# lpf.net
KiCad netlist of a schematic drawn in Altium Designer
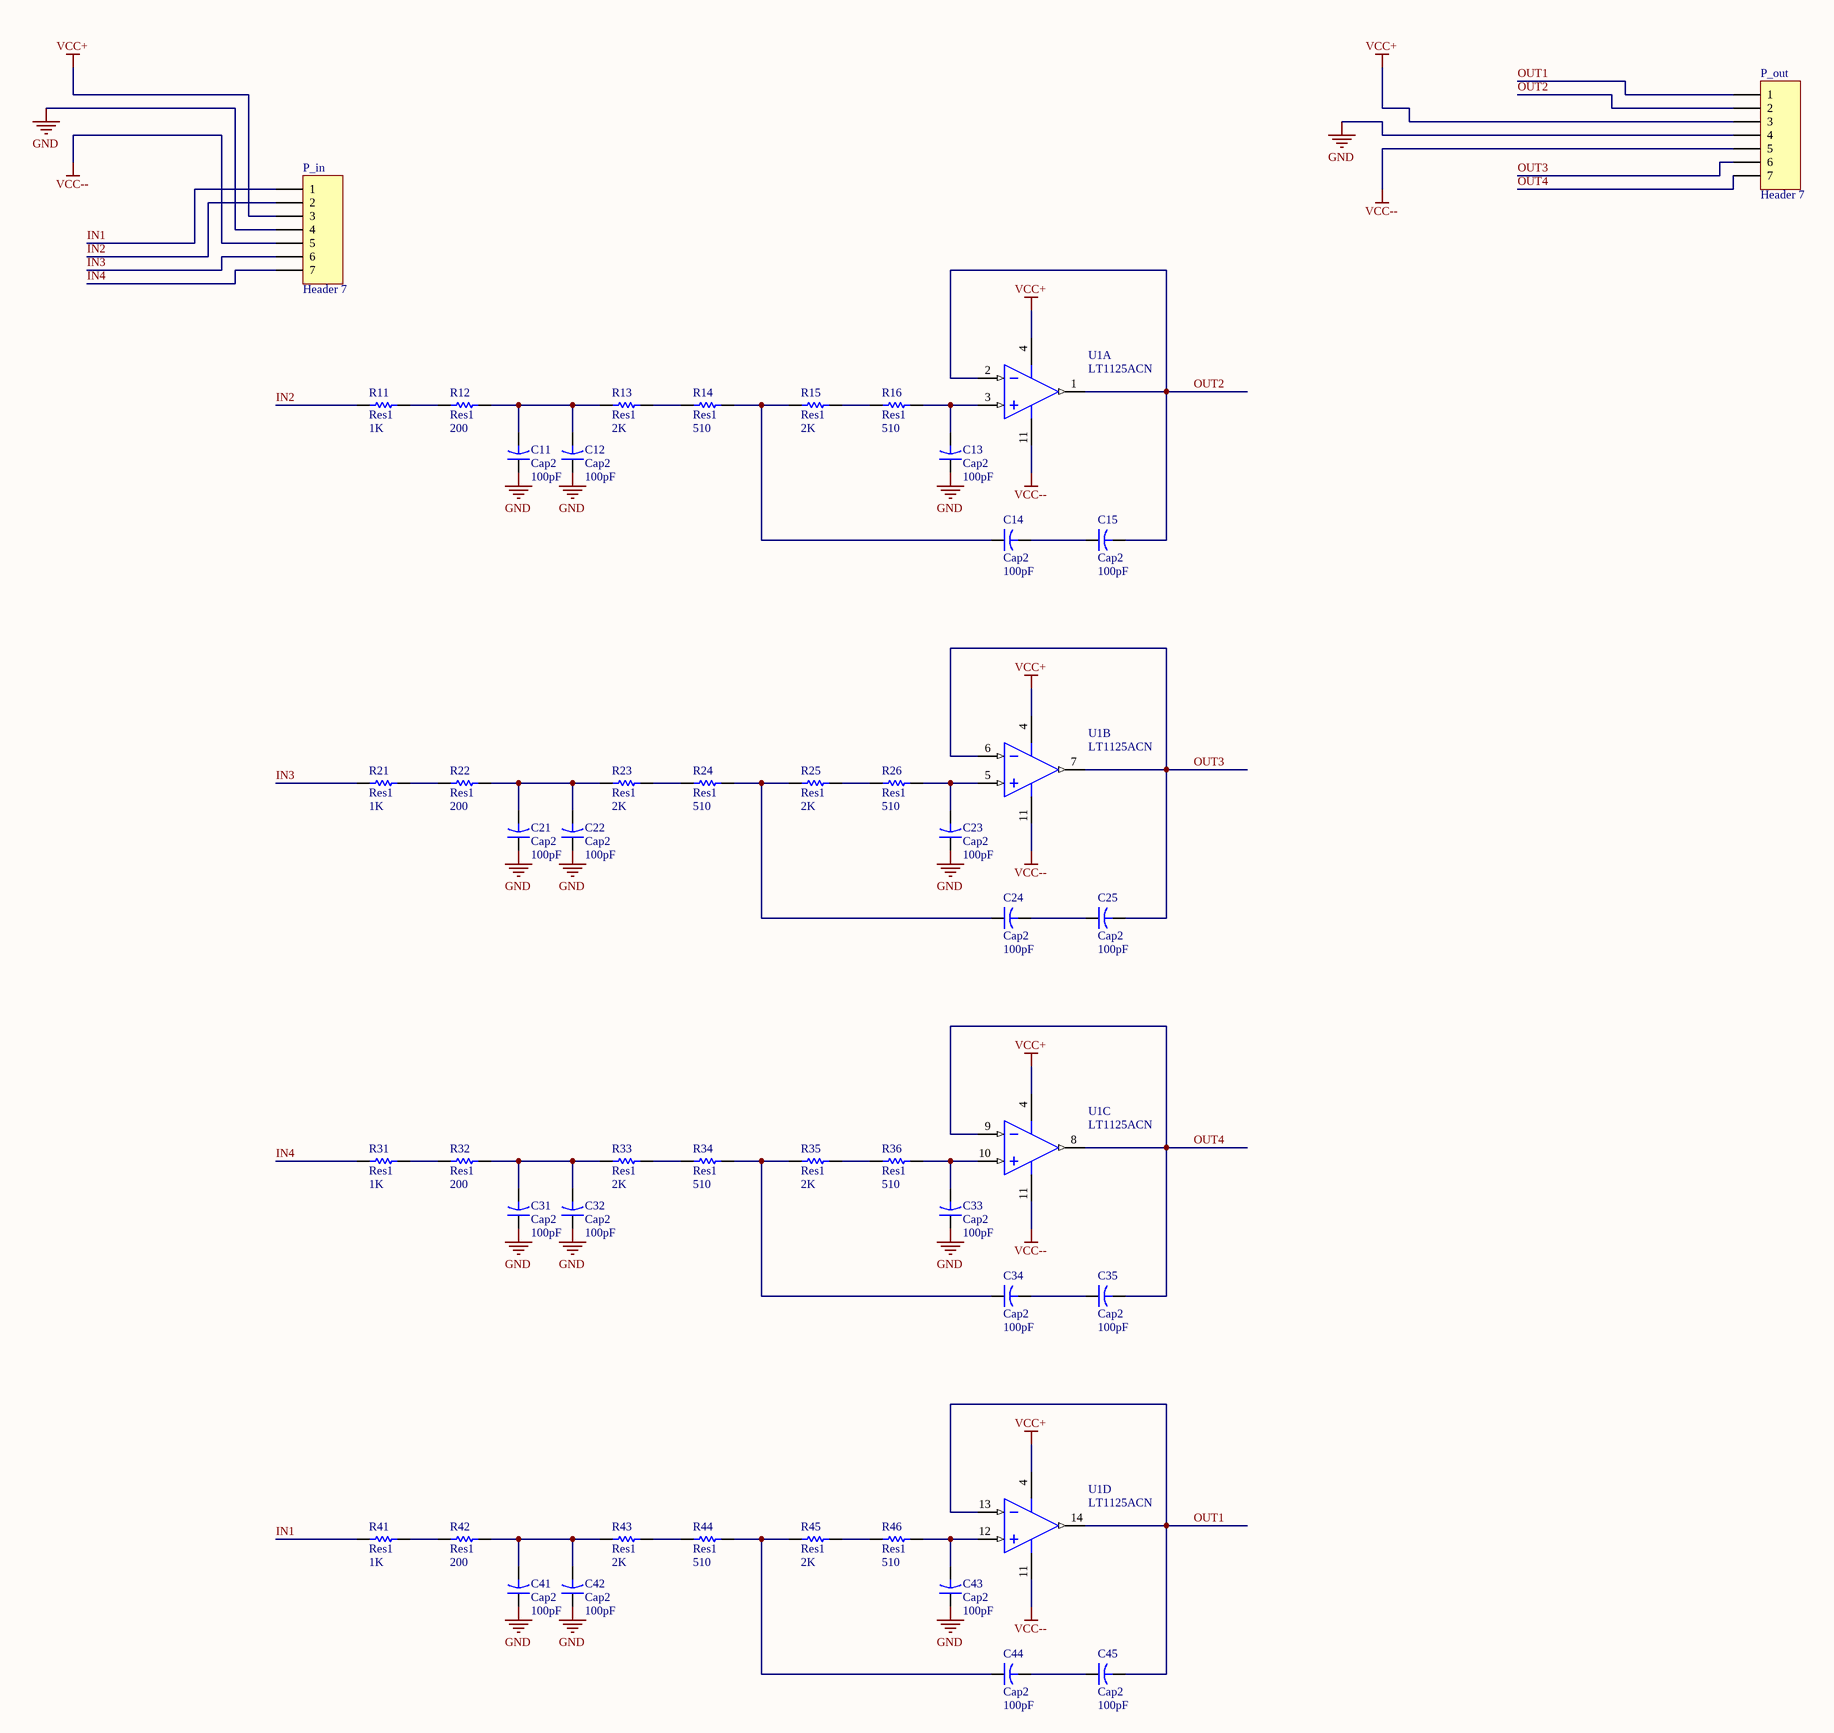
[diagram p0: lpf.SchDoc]

(export (version "E")
  (design (tool "Eeschema 10.0.6"))
  (components
    (comp (ref "C11")
      (value "Cap2")
      (footprint "CAPR5-4X5")
      (description "Capacitor")
      (fields (field (name "ALTIUM_VALUE") "100pF") (field (name "PUBLISHER") "Altium Limited"))
      (libsource (lib "Miscellaneous Devices") (part "Cap2"))
    )
    (comp (ref "C12")
      (value "Cap2")
      (footprint "CAPR5-4X5")
      (description "Capacitor")
      (fields (field (name "ALTIUM_VALUE") "100pF") (field (name "PUBLISHER") "Altium Limited"))
      (libsource (lib "Miscellaneous Devices") (part "Cap2"))
    )
    (comp (ref "C13")
      (value "Cap2")
      (footprint "CAPR5-4X5")
      (description "Capacitor")
      (fields (field (name "ALTIUM_VALUE") "100pF") (field (name "PUBLISHER") "Altium Limited"))
      (libsource (lib "Miscellaneous Devices") (part "Cap2"))
    )
    (comp (ref "C14")
      (value "Cap2")
      (footprint "CAPR5-4X5")
      (description "Capacitor")
      (fields (field (name "ALTIUM_VALUE") "100pF") (field (name "PUBLISHER") "Altium Limited"))
      (libsource (lib "Miscellaneous Devices") (part "Cap2"))
    )
    (comp (ref "C15")
      (value "Cap2")
      (footprint "CAPR5-4X5")
      (description "Capacitor")
      (fields (field (name "ALTIUM_VALUE") "100pF") (field (name "PUBLISHER") "Altium Limited"))
      (libsource (lib "Miscellaneous Devices") (part "Cap2"))
    )
    (comp (ref "C21")
      (value "Cap2")
      (footprint "CAPR5-4X5")
      (description "Capacitor")
      (fields (field (name "ALTIUM_VALUE") "100pF") (field (name "PUBLISHER") "Altium Limited"))
      (libsource (lib "Miscellaneous Devices") (part "Cap2"))
    )
    (comp (ref "C22")
      (value "Cap2")
      (footprint "CAPR5-4X5")
      (description "Capacitor")
      (fields (field (name "ALTIUM_VALUE") "100pF") (field (name "PUBLISHER") "Altium Limited"))
      (libsource (lib "Miscellaneous Devices") (part "Cap2"))
    )
    (comp (ref "C23")
      (value "Cap2")
      (footprint "CAPR5-4X5")
      (description "Capacitor")
      (fields (field (name "ALTIUM_VALUE") "100pF") (field (name "PUBLISHER") "Altium Limited"))
      (libsource (lib "Miscellaneous Devices") (part "Cap2"))
    )
    (comp (ref "C24")
      (value "Cap2")
      (footprint "CAPR5-4X5")
      (description "Capacitor")
      (fields (field (name "ALTIUM_VALUE") "100pF") (field (name "PUBLISHER") "Altium Limited"))
      (libsource (lib "Miscellaneous Devices") (part "Cap2"))
    )
    (comp (ref "C25")
      (value "Cap2")
      (footprint "CAPR5-4X5")
      (description "Capacitor")
      (fields (field (name "ALTIUM_VALUE") "100pF") (field (name "PUBLISHER") "Altium Limited"))
      (libsource (lib "Miscellaneous Devices") (part "Cap2"))
    )
    (comp (ref "C31")
      (value "Cap2")
      (footprint "CAPR5-4X5")
      (description "Capacitor")
      (fields (field (name "ALTIUM_VALUE") "100pF") (field (name "PUBLISHER") "Altium Limited"))
      (libsource (lib "Miscellaneous Devices") (part "Cap2"))
    )
    (comp (ref "C32")
      (value "Cap2")
      (footprint "CAPR5-4X5")
      (description "Capacitor")
      (fields (field (name "ALTIUM_VALUE") "100pF") (field (name "PUBLISHER") "Altium Limited"))
      (libsource (lib "Miscellaneous Devices") (part "Cap2"))
    )
    (comp (ref "C33")
      (value "Cap2")
      (footprint "CAPR5-4X5")
      (description "Capacitor")
      (fields (field (name "ALTIUM_VALUE") "100pF") (field (name "PUBLISHER") "Altium Limited"))
      (libsource (lib "Miscellaneous Devices") (part "Cap2"))
    )
    (comp (ref "C34")
      (value "Cap2")
      (footprint "CAPR5-4X5")
      (description "Capacitor")
      (fields (field (name "ALTIUM_VALUE") "100pF") (field (name "PUBLISHER") "Altium Limited"))
      (libsource (lib "Miscellaneous Devices") (part "Cap2"))
    )
    (comp (ref "C35")
      (value "Cap2")
      (footprint "CAPR5-4X5")
      (description "Capacitor")
      (fields (field (name "ALTIUM_VALUE") "100pF") (field (name "PUBLISHER") "Altium Limited"))
      (libsource (lib "Miscellaneous Devices") (part "Cap2"))
    )
    (comp (ref "C41")
      (value "Cap2")
      (footprint "CAPR5-4X5")
      (description "Capacitor")
      (fields (field (name "ALTIUM_VALUE") "100pF") (field (name "PUBLISHER") "Altium Limited"))
      (libsource (lib "Miscellaneous Devices") (part "Cap2"))
    )
    (comp (ref "C42")
      (value "Cap2")
      (footprint "CAPR5-4X5")
      (description "Capacitor")
      (fields (field (name "ALTIUM_VALUE") "100pF") (field (name "PUBLISHER") "Altium Limited"))
      (libsource (lib "Miscellaneous Devices") (part "Cap2"))
    )
    (comp (ref "C43")
      (value "Cap2")
      (footprint "CAPR5-4X5")
      (description "Capacitor")
      (fields (field (name "ALTIUM_VALUE") "100pF") (field (name "PUBLISHER") "Altium Limited"))
      (libsource (lib "Miscellaneous Devices") (part "Cap2"))
    )
    (comp (ref "C44")
      (value "Cap2")
      (footprint "CAPR5-4X5")
      (description "Capacitor")
      (fields (field (name "ALTIUM_VALUE") "100pF") (field (name "PUBLISHER") "Altium Limited"))
      (libsource (lib "Miscellaneous Devices") (part "Cap2"))
    )
    (comp (ref "C45")
      (value "Cap2")
      (footprint "CAPR5-4X5")
      (description "Capacitor")
      (fields (field (name "ALTIUM_VALUE") "100pF") (field (name "PUBLISHER") "Altium Limited"))
      (libsource (lib "Miscellaneous Devices") (part "Cap2"))
    )
    (comp (ref "P_in")
      (value "Header 7")
      (footprint "HDR1X7")
      (description "Header, 7-Pin")
      (fields (field (name "PUBLISHER") "Altium Limited"))
      (libsource (lib "Miscellaneous Connectors") (part "Header 7"))
    )
    (comp (ref "P_out")
      (value "Header 7")
      (footprint "HDR1X7")
      (description "Header, 7-Pin")
      (fields (field (name "PUBLISHER") "Altium Limited"))
      (libsource (lib "Miscellaneous Connectors") (part "Header 7"))
    )
    (comp (ref "R11")
      (value "Res1")
      (footprint "AXIAL-0.3")
      (description "Resistor")
      (fields (field (name "ALTIUM_VALUE") "1K") (field (name "PUBLISHER") "Altium Limited"))
      (libsource (lib "Miscellaneous Devices") (part "Res1"))
    )
    (comp (ref "R12")
      (value "Res1")
      (footprint "AXIAL-0.3")
      (description "Resistor")
      (fields (field (name "ALTIUM_VALUE") "200") (field (name "PUBLISHER") "Altium Limited"))
      (libsource (lib "Miscellaneous Devices") (part "Res1"))
    )
    (comp (ref "R13")
      (value "Res1")
      (footprint "AXIAL-0.3")
      (description "Resistor")
      (fields (field (name "ALTIUM_VALUE") "2K") (field (name "PUBLISHER") "Altium Limited"))
      (libsource (lib "Miscellaneous Devices") (part "Res1"))
    )
    (comp (ref "R14")
      (value "Res1")
      (footprint "AXIAL-0.3")
      (description "Resistor")
      (fields (field (name "ALTIUM_VALUE") "510") (field (name "PUBLISHER") "Altium Limited"))
      (libsource (lib "Miscellaneous Devices") (part "Res1"))
    )
    (comp (ref "R15")
      (value "Res1")
      (footprint "AXIAL-0.3")
      (description "Resistor")
      (fields (field (name "ALTIUM_VALUE") "2K") (field (name "PUBLISHER") "Altium Limited"))
      (libsource (lib "Miscellaneous Devices") (part "Res1"))
    )
    (comp (ref "R16")
      (value "Res1")
      (footprint "AXIAL-0.3")
      (description "Resistor")
      (fields (field (name "ALTIUM_VALUE") "510") (field (name "PUBLISHER") "Altium Limited"))
      (libsource (lib "Miscellaneous Devices") (part "Res1"))
    )
    (comp (ref "R21")
      (value "Res1")
      (footprint "AXIAL-0.3")
      (description "Resistor")
      (fields (field (name "ALTIUM_VALUE") "1K") (field (name "PUBLISHER") "Altium Limited"))
      (libsource (lib "Miscellaneous Devices") (part "Res1"))
    )
    (comp (ref "R22")
      (value "Res1")
      (footprint "AXIAL-0.3")
      (description "Resistor")
      (fields (field (name "ALTIUM_VALUE") "200") (field (name "PUBLISHER") "Altium Limited"))
      (libsource (lib "Miscellaneous Devices") (part "Res1"))
    )
    (comp (ref "R23")
      (value "Res1")
      (footprint "AXIAL-0.3")
      (description "Resistor")
      (fields (field (name "ALTIUM_VALUE") "2K") (field (name "PUBLISHER") "Altium Limited"))
      (libsource (lib "Miscellaneous Devices") (part "Res1"))
    )
    (comp (ref "R24")
      (value "Res1")
      (footprint "AXIAL-0.3")
      (description "Resistor")
      (fields (field (name "ALTIUM_VALUE") "510") (field (name "PUBLISHER") "Altium Limited"))
      (libsource (lib "Miscellaneous Devices") (part "Res1"))
    )
    (comp (ref "R25")
      (value "Res1")
      (footprint "AXIAL-0.3")
      (description "Resistor")
      (fields (field (name "ALTIUM_VALUE") "2K") (field (name "PUBLISHER") "Altium Limited"))
      (libsource (lib "Miscellaneous Devices") (part "Res1"))
    )
    (comp (ref "R26")
      (value "Res1")
      (footprint "AXIAL-0.3")
      (description "Resistor")
      (fields (field (name "ALTIUM_VALUE") "510") (field (name "PUBLISHER") "Altium Limited"))
      (libsource (lib "Miscellaneous Devices") (part "Res1"))
    )
    (comp (ref "R31")
      (value "Res1")
      (footprint "AXIAL-0.3")
      (description "Resistor")
      (fields (field (name "ALTIUM_VALUE") "1K") (field (name "PUBLISHER") "Altium Limited"))
      (libsource (lib "Miscellaneous Devices") (part "Res1"))
    )
    (comp (ref "R32")
      (value "Res1")
      (footprint "AXIAL-0.3")
      (description "Resistor")
      (fields (field (name "ALTIUM_VALUE") "200") (field (name "PUBLISHER") "Altium Limited"))
      (libsource (lib "Miscellaneous Devices") (part "Res1"))
    )
    (comp (ref "R33")
      (value "Res1")
      (footprint "AXIAL-0.3")
      (description "Resistor")
      (fields (field (name "ALTIUM_VALUE") "2K") (field (name "PUBLISHER") "Altium Limited"))
      (libsource (lib "Miscellaneous Devices") (part "Res1"))
    )
    (comp (ref "R34")
      (value "Res1")
      (footprint "AXIAL-0.3")
      (description "Resistor")
      (fields (field (name "ALTIUM_VALUE") "510") (field (name "PUBLISHER") "Altium Limited"))
      (libsource (lib "Miscellaneous Devices") (part "Res1"))
    )
    (comp (ref "R35")
      (value "Res1")
      (footprint "AXIAL-0.3")
      (description "Resistor")
      (fields (field (name "ALTIUM_VALUE") "2K") (field (name "PUBLISHER") "Altium Limited"))
      (libsource (lib "Miscellaneous Devices") (part "Res1"))
    )
    (comp (ref "R36")
      (value "Res1")
      (footprint "AXIAL-0.3")
      (description "Resistor")
      (fields (field (name "ALTIUM_VALUE") "510") (field (name "PUBLISHER") "Altium Limited"))
      (libsource (lib "Miscellaneous Devices") (part "Res1"))
    )
    (comp (ref "R41")
      (value "Res1")
      (footprint "AXIAL-0.3")
      (description "Resistor")
      (fields (field (name "ALTIUM_VALUE") "1K") (field (name "PUBLISHER") "Altium Limited"))
      (libsource (lib "Miscellaneous Devices") (part "Res1"))
    )
    (comp (ref "R42")
      (value "Res1")
      (footprint "AXIAL-0.3")
      (description "Resistor")
      (fields (field (name "ALTIUM_VALUE") "200") (field (name "PUBLISHER") "Altium Limited"))
      (libsource (lib "Miscellaneous Devices") (part "Res1"))
    )
    (comp (ref "R43")
      (value "Res1")
      (footprint "AXIAL-0.3")
      (description "Resistor")
      (fields (field (name "ALTIUM_VALUE") "2K") (field (name "PUBLISHER") "Altium Limited"))
      (libsource (lib "Miscellaneous Devices") (part "Res1"))
    )
    (comp (ref "R44")
      (value "Res1")
      (footprint "AXIAL-0.3")
      (description "Resistor")
      (fields (field (name "ALTIUM_VALUE") "510") (field (name "PUBLISHER") "Altium Limited"))
      (libsource (lib "Miscellaneous Devices") (part "Res1"))
    )
    (comp (ref "R45")
      (value "Res1")
      (footprint "AXIAL-0.3")
      (description "Resistor")
      (fields (field (name "ALTIUM_VALUE") "2K") (field (name "PUBLISHER") "Altium Limited"))
      (libsource (lib "Miscellaneous Devices") (part "Res1"))
    )
    (comp (ref "R46")
      (value "Res1")
      (footprint "AXIAL-0.3")
      (description "Resistor")
      (fields (field (name "ALTIUM_VALUE") "510") (field (name "PUBLISHER") "Altium Limited"))
      (libsource (lib "Miscellaneous Devices") (part "Res1"))
    )
    (comp (ref "U1")
      (value "LT1125ACN")
      (footprint "LT-N-14")
      (fields
        (field (name "LINEAR TECHNOLOGY PART NUMBER") "LT1125")
        (field (name "MANUFACTURER") "Linear Technology")
      )
      (libsource (lib "Linear Technology Operational Amplifiers (LT1000)") (part "LT1125ACN"))
    )
  )
  (nets
    (net (code "1") (name "/IN1") (class "Default")
      (node (ref "P_in") (pin "1") (pinfunction "1_1") (pintype "passive"))
      (node (ref "R41") (pin "1") (pinfunction "1_1") (pintype "passive"))
    )
    (net (code "2") (name "/IN2") (class "Default")
      (node (ref "P_in") (pin "2") (pinfunction "2_2") (pintype "passive"))
      (node (ref "R11") (pin "1") (pinfunction "1_1") (pintype "passive"))
    )
    (net (code "3") (name "/IN3") (class "Default")
      (node (ref "P_in") (pin "6") (pinfunction "6_6") (pintype "passive"))
      (node (ref "R21") (pin "1") (pinfunction "1_1") (pintype "passive"))
    )
    (net (code "4") (name "/IN4") (class "Default")
      (node (ref "P_in") (pin "7") (pinfunction "7_7") (pintype "passive"))
      (node (ref "R31") (pin "1") (pinfunction "1_1") (pintype "passive"))
    )
    (net (code "5") (name "/OUT1") (class "Default")
      (node (ref "C45") (pin "2") (pinfunction "2_2") (pintype "passive"))
      (node (ref "P_out") (pin "1") (pinfunction "1_1") (pintype "passive"))
      (node (ref "U1") (pin "13") (pinfunction "-IND_13") (pintype "input"))
      (node (ref "U1") (pin "14") (pinfunction "OUTD_14") (pintype "output"))
    )
    (net (code "6") (name "/OUT2") (class "Default")
      (node (ref "C15") (pin "2") (pinfunction "2_2") (pintype "passive"))
      (node (ref "P_out") (pin "2") (pinfunction "2_2") (pintype "passive"))
      (node (ref "U1") (pin "1") (pinfunction "OUTA_1") (pintype "output"))
      (node (ref "U1") (pin "2") (pinfunction "-INA_2") (pintype "input"))
    )
    (net (code "7") (name "/OUT3") (class "Default")
      (node (ref "C25") (pin "2") (pinfunction "2_2") (pintype "passive"))
      (node (ref "P_out") (pin "6") (pinfunction "6_6") (pintype "passive"))
      (node (ref "U1") (pin "6") (pinfunction "-INB_6") (pintype "input"))
      (node (ref "U1") (pin "7") (pinfunction "OUTB_7") (pintype "output"))
    )
    (net (code "8") (name "/OUT4") (class "Default")
      (node (ref "C35") (pin "2") (pinfunction "2_2") (pintype "passive"))
      (node (ref "P_out") (pin "7") (pinfunction "7_7") (pintype "passive"))
      (node (ref "U1") (pin "8") (pinfunction "OUTC_8") (pintype "output"))
      (node (ref "U1") (pin "9") (pinfunction "-INC_9") (pintype "input"))
    )
    (net (code "9") (name "GND") (class "Default")
      (node (ref "C11") (pin "1") (pinfunction "1_1") (pintype "passive"))
      (node (ref "C12") (pin "1") (pinfunction "1_1") (pintype "passive"))
      (node (ref "C13") (pin "1") (pinfunction "1_1") (pintype "passive"))
      (node (ref "C21") (pin "1") (pinfunction "1_1") (pintype "passive"))
      (node (ref "C22") (pin "1") (pinfunction "1_1") (pintype "passive"))
      (node (ref "C23") (pin "1") (pinfunction "1_1") (pintype "passive"))
      (node (ref "C31") (pin "1") (pinfunction "1_1") (pintype "passive"))
      (node (ref "C32") (pin "1") (pinfunction "1_1") (pintype "passive"))
      (node (ref "C33") (pin "1") (pinfunction "1_1") (pintype "passive"))
      (node (ref "C41") (pin "1") (pinfunction "1_1") (pintype "passive"))
      (node (ref "C42") (pin "1") (pinfunction "1_1") (pintype "passive"))
      (node (ref "C43") (pin "1") (pinfunction "1_1") (pintype "passive"))
      (node (ref "P_in") (pin "4") (pinfunction "4_4") (pintype "passive"))
      (node (ref "P_out") (pin "4") (pinfunction "4_4") (pintype "passive"))
    )
    (net (code "10") (name "Net-(C11-Pad2)") (class "Default")
      (node (ref "C11") (pin "2") (pinfunction "2_2") (pintype "passive"))
      (node (ref "C12") (pin "2") (pinfunction "2_2") (pintype "passive"))
      (node (ref "R12") (pin "2") (pinfunction "2_2") (pintype "passive"))
      (node (ref "R13") (pin "1") (pinfunction "1_1") (pintype "passive"))
    )
    (net (code "11") (name "Net-(C14-Pad1)") (class "Default")
      (node (ref "C14") (pin "1") (pinfunction "1_1") (pintype "passive"))
      (node (ref "R14") (pin "2") (pinfunction "2_2") (pintype "passive"))
      (node (ref "R15") (pin "1") (pinfunction "1_1") (pintype "passive"))
    )
    (net (code "12") (name "Net-(C14-Pad2)") (class "Default")
      (node (ref "C14") (pin "2") (pinfunction "2_2") (pintype "passive"))
      (node (ref "C15") (pin "1") (pinfunction "1_1") (pintype "passive"))
    )
    (net (code "13") (name "Net-(C21-Pad2)") (class "Default")
      (node (ref "C21") (pin "2") (pinfunction "2_2") (pintype "passive"))
      (node (ref "C22") (pin "2") (pinfunction "2_2") (pintype "passive"))
      (node (ref "R22") (pin "2") (pinfunction "2_2") (pintype "passive"))
      (node (ref "R23") (pin "1") (pinfunction "1_1") (pintype "passive"))
    )
    (net (code "14") (name "Net-(C24-Pad1)") (class "Default")
      (node (ref "C24") (pin "1") (pinfunction "1_1") (pintype "passive"))
      (node (ref "R24") (pin "2") (pinfunction "2_2") (pintype "passive"))
      (node (ref "R25") (pin "1") (pinfunction "1_1") (pintype "passive"))
    )
    (net (code "15") (name "Net-(C24-Pad2)") (class "Default")
      (node (ref "C24") (pin "2") (pinfunction "2_2") (pintype "passive"))
      (node (ref "C25") (pin "1") (pinfunction "1_1") (pintype "passive"))
    )
    (net (code "16") (name "Net-(C31-Pad2)") (class "Default")
      (node (ref "C31") (pin "2") (pinfunction "2_2") (pintype "passive"))
      (node (ref "C32") (pin "2") (pinfunction "2_2") (pintype "passive"))
      (node (ref "R32") (pin "2") (pinfunction "2_2") (pintype "passive"))
      (node (ref "R33") (pin "1") (pinfunction "1_1") (pintype "passive"))
    )
    (net (code "17") (name "Net-(C34-Pad1)") (class "Default")
      (node (ref "C34") (pin "1") (pinfunction "1_1") (pintype "passive"))
      (node (ref "R34") (pin "2") (pinfunction "2_2") (pintype "passive"))
      (node (ref "R35") (pin "1") (pinfunction "1_1") (pintype "passive"))
    )
    (net (code "18") (name "Net-(C34-Pad2)") (class "Default")
      (node (ref "C34") (pin "2") (pinfunction "2_2") (pintype "passive"))
      (node (ref "C35") (pin "1") (pinfunction "1_1") (pintype "passive"))
    )
    (net (code "19") (name "Net-(C41-Pad2)") (class "Default")
      (node (ref "C41") (pin "2") (pinfunction "2_2") (pintype "passive"))
      (node (ref "C42") (pin "2") (pinfunction "2_2") (pintype "passive"))
      (node (ref "R42") (pin "2") (pinfunction "2_2") (pintype "passive"))
      (node (ref "R43") (pin "1") (pinfunction "1_1") (pintype "passive"))
    )
    (net (code "20") (name "Net-(C44-Pad1)") (class "Default")
      (node (ref "C44") (pin "1") (pinfunction "1_1") (pintype "passive"))
      (node (ref "R44") (pin "2") (pinfunction "2_2") (pintype "passive"))
      (node (ref "R45") (pin "1") (pinfunction "1_1") (pintype "passive"))
    )
    (net (code "21") (name "Net-(C44-Pad2)") (class "Default")
      (node (ref "C44") (pin "2") (pinfunction "2_2") (pintype "passive"))
      (node (ref "C45") (pin "1") (pinfunction "1_1") (pintype "passive"))
    )
    (net (code "22") (name "Net-(R11-Pad2)") (class "Default")
      (node (ref "R11") (pin "2") (pinfunction "2_2") (pintype "passive"))
      (node (ref "R12") (pin "1") (pinfunction "1_1") (pintype "passive"))
    )
    (net (code "23") (name "Net-(R13-Pad2)") (class "Default")
      (node (ref "R13") (pin "2") (pinfunction "2_2") (pintype "passive"))
      (node (ref "R14") (pin "1") (pinfunction "1_1") (pintype "passive"))
    )
    (net (code "24") (name "Net-(R15-Pad2)") (class "Default")
      (node (ref "R15") (pin "2") (pinfunction "2_2") (pintype "passive"))
      (node (ref "R16") (pin "1") (pinfunction "1_1") (pintype "passive"))
    )
    (net (code "25") (name "Net-(R21-Pad2)") (class "Default")
      (node (ref "R21") (pin "2") (pinfunction "2_2") (pintype "passive"))
      (node (ref "R22") (pin "1") (pinfunction "1_1") (pintype "passive"))
    )
    (net (code "26") (name "Net-(R23-Pad2)") (class "Default")
      (node (ref "R23") (pin "2") (pinfunction "2_2") (pintype "passive"))
      (node (ref "R24") (pin "1") (pinfunction "1_1") (pintype "passive"))
    )
    (net (code "27") (name "Net-(R25-Pad2)") (class "Default")
      (node (ref "R25") (pin "2") (pinfunction "2_2") (pintype "passive"))
      (node (ref "R26") (pin "1") (pinfunction "1_1") (pintype "passive"))
    )
    (net (code "28") (name "Net-(R31-Pad2)") (class "Default")
      (node (ref "R31") (pin "2") (pinfunction "2_2") (pintype "passive"))
      (node (ref "R32") (pin "1") (pinfunction "1_1") (pintype "passive"))
    )
    (net (code "29") (name "Net-(R33-Pad2)") (class "Default")
      (node (ref "R33") (pin "2") (pinfunction "2_2") (pintype "passive"))
      (node (ref "R34") (pin "1") (pinfunction "1_1") (pintype "passive"))
    )
    (net (code "30") (name "Net-(R35-Pad2)") (class "Default")
      (node (ref "R35") (pin "2") (pinfunction "2_2") (pintype "passive"))
      (node (ref "R36") (pin "1") (pinfunction "1_1") (pintype "passive"))
    )
    (net (code "31") (name "Net-(R41-Pad2)") (class "Default")
      (node (ref "R41") (pin "2") (pinfunction "2_2") (pintype "passive"))
      (node (ref "R42") (pin "1") (pinfunction "1_1") (pintype "passive"))
    )
    (net (code "32") (name "Net-(R43-Pad2)") (class "Default")
      (node (ref "R43") (pin "2") (pinfunction "2_2") (pintype "passive"))
      (node (ref "R44") (pin "1") (pinfunction "1_1") (pintype "passive"))
    )
    (net (code "33") (name "Net-(R45-Pad2)") (class "Default")
      (node (ref "R45") (pin "2") (pinfunction "2_2") (pintype "passive"))
      (node (ref "R46") (pin "1") (pinfunction "1_1") (pintype "passive"))
    )
    (net (code "34") (name "Net-(U1A-+INA)") (class "Default")
      (node (ref "C13") (pin "2") (pinfunction "2_2") (pintype "passive"))
      (node (ref "R16") (pin "2") (pinfunction "2_2") (pintype "passive"))
      (node (ref "U1") (pin "3") (pinfunction "+INA_3") (pintype "input"))
    )
    (net (code "35") (name "Net-(U1B-+INB)") (class "Default")
      (node (ref "C23") (pin "2") (pinfunction "2_2") (pintype "passive"))
      (node (ref "R26") (pin "2") (pinfunction "2_2") (pintype "passive"))
      (node (ref "U1") (pin "5") (pinfunction "+INB_5") (pintype "input"))
    )
    (net (code "36") (name "Net-(U1C-+INC)") (class "Default")
      (node (ref "C33") (pin "2") (pinfunction "2_2") (pintype "passive"))
      (node (ref "R36") (pin "2") (pinfunction "2_2") (pintype "passive"))
      (node (ref "U1") (pin "10") (pinfunction "+INC_10") (pintype "input"))
    )
    (net (code "37") (name "Net-(U1D-+IND)") (class "Default")
      (node (ref "C43") (pin "2") (pinfunction "2_2") (pintype "passive"))
      (node (ref "R46") (pin "2") (pinfunction "2_2") (pintype "passive"))
      (node (ref "U1") (pin "12") (pinfunction "+IND_12") (pintype "input"))
    )
    (net (code "38") (name "VCC+") (class "Default")
      (node (ref "P_in") (pin "3") (pinfunction "3_3") (pintype "passive"))
      (node (ref "P_out") (pin "3") (pinfunction "3_3") (pintype "passive"))
      (node (ref "U1") (pin "4") (pinfunction "V+_4") (pintype "power_in"))
    )
    (net (code "39") (name "VCC--") (class "Default")
      (node (ref "P_in") (pin "5") (pinfunction "5_5") (pintype "passive"))
      (node (ref "P_out") (pin "5") (pinfunction "5_5") (pintype "passive"))
      (node (ref "U1") (pin "11") (pinfunction "V-_11") (pintype "power_in"))
    )
  )
)
